# audio_board.net
KiCad netlist of a schematic drawn in EAGLE
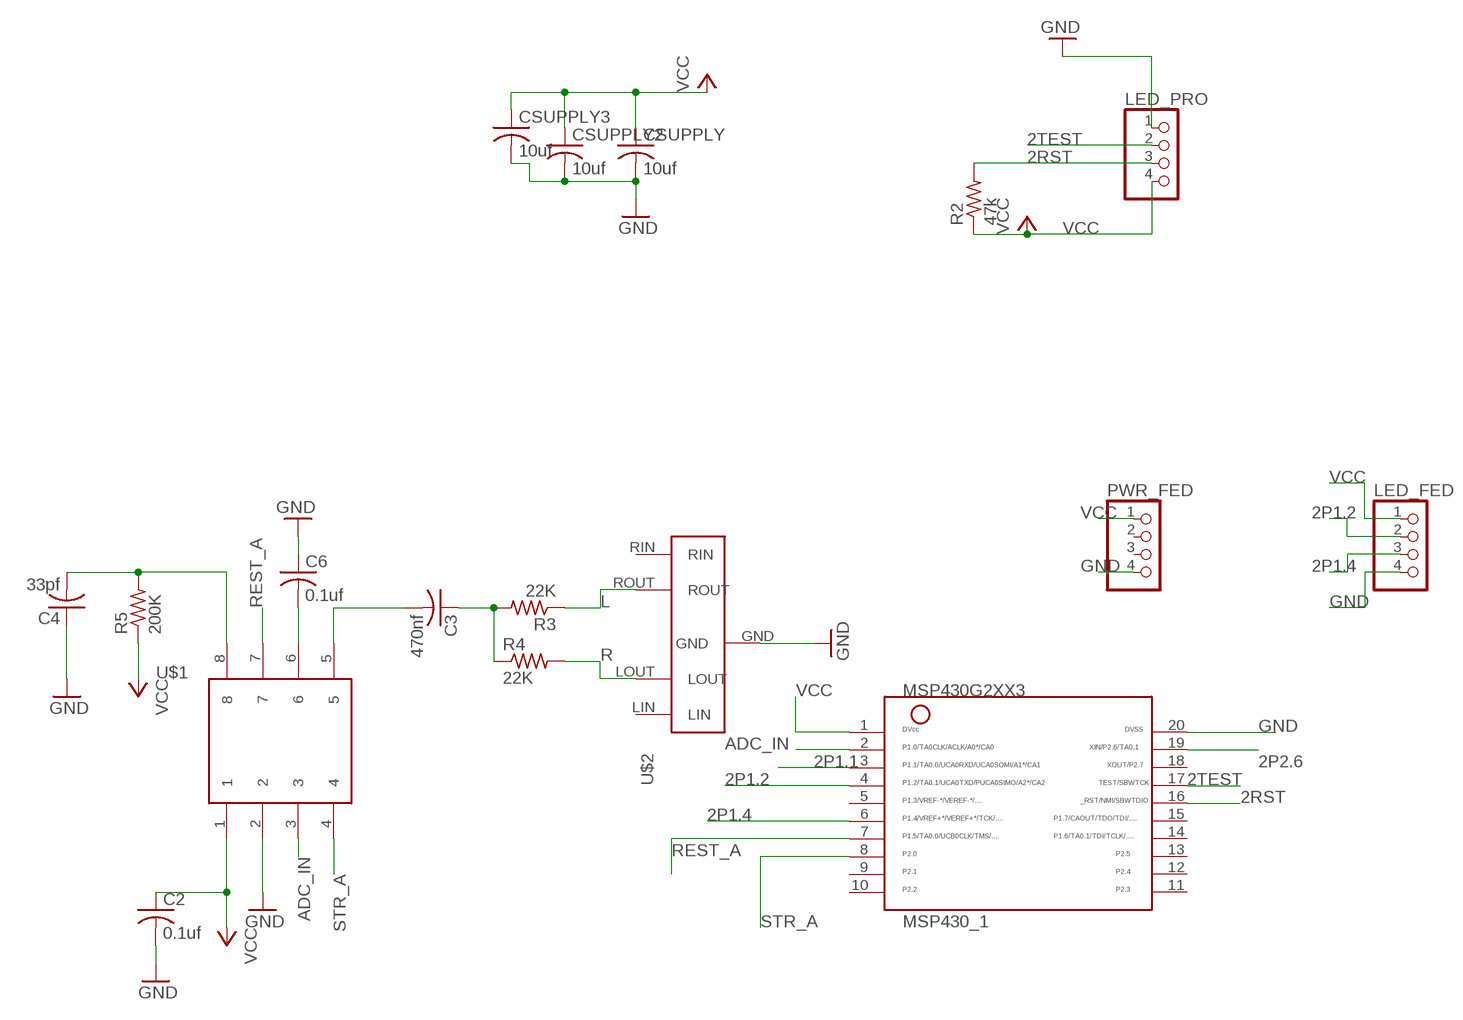
[diagram p0: schematic, sheet 1]

(export (version "E")
  (design (tool "Eeschema 10.0.6"))
  (components
    (comp (ref "C2")
      (value "0.1uf")
      (footprint "eagle-import:C1206")
      (libsource (lib "eagle-import") (part "C-USC1206"))
    )
    (comp (ref "C3")
      (value "470nf")
      (footprint "eagle-import:C1206")
      (libsource (lib "eagle-import") (part "C-USC1206"))
    )
    (comp (ref "C4")
      (value "33pf")
      (footprint "eagle-import:C1206")
      (libsource (lib "eagle-import") (part "C-USC1206"))
    )
    (comp (ref "C6")
      (value "0.1uf")
      (footprint "eagle-import:C1206")
      (libsource (lib "eagle-import") (part "C-USC1206"))
    )
    (comp (ref "CSUPPLY")
      (value "10uf")
      (footprint "eagle-import:C1206")
      (libsource (lib "eagle-import") (part "C-USC1206"))
    )
    (comp (ref "CSUPPLY2")
      (value "10uf")
      (footprint "eagle-import:C1206")
      (libsource (lib "eagle-import") (part "C-USC1206"))
    )
    (comp (ref "CSUPPLY3")
      (value "10uf")
      (footprint "eagle-import:C1206")
      (libsource (lib "eagle-import") (part "C-USC1206"))
    )
    (comp (ref "LED_FED")
      (value "PINHD-1X4")
      (footprint "eagle-import:1X04")
      (libsource (lib "eagle-import") (part "PINHD-1X4"))
    )
    (comp (ref "LED_PRO")
      (value "PINHD-1X4")
      (footprint "eagle-import:1X04")
      (libsource (lib "eagle-import") (part "PINHD-1X4"))
    )
    (comp (ref "MSP430_1")
      (value "MSP430G2XX3TSSOP")
      (footprint "eagle-import:PW20")
      (libsource (lib "eagle-import") (part "MSP430G2XX3TSSOP"))
    )
    (comp (ref "PWR_FED")
      (value "PINHD-1X4")
      (footprint "eagle-import:1X04")
      (libsource (lib "eagle-import") (part "PINHD-1X4"))
    )
    (comp (ref "R2")
      (value "47k")
      (footprint "eagle-import:R1206")
      (libsource (lib "eagle-import") (part "R-US_R1206"))
    )
    (comp (ref "R3")
      (value "22K")
      (footprint "eagle-import:R1206")
      (libsource (lib "eagle-import") (part "R-US_R1206"))
    )
    (comp (ref "R4")
      (value "22K")
      (footprint "eagle-import:R1206")
      (libsource (lib "eagle-import") (part "R-US_R1206"))
    )
    (comp (ref "R5")
      (value "200K")
      (footprint "eagle-import:R1206")
      (libsource (lib "eagle-import") (part "R-US_R1206"))
    )
    (comp (ref "U$1")
      (value "MSGEQ7")
      (footprint "eagle-import:MSGEQ7")
      (libsource (lib "eagle-import") (part "MSGEQ7"))
    )
    (comp (ref "U$2")
      (value "1699_HEAD")
      (footprint "eagle-import:1699_HEAD")
      (libsource (lib "eagle-import") (part "1699_HEAD"))
    )
  )
  (nets
    (net (code "1") (name "/2P1.1") (class "Default")
      (node (ref "MSP430_1") (pin "3") (pinfunction "3_3") (pintype "bidirectional"))
    )
    (net (code "2") (name "/2P1.2") (class "Default")
      (node (ref "LED_FED") (pin "2") (pinfunction "2_2") (pintype "passive"))
      (node (ref "MSP430_1") (pin "4") (pinfunction "4_4") (pintype "bidirectional"))
    )
    (net (code "3") (name "/2P1.4") (class "Default")
      (node (ref "LED_FED") (pin "3") (pinfunction "3_3") (pintype "passive"))
      (node (ref "MSP430_1") (pin "6") (pinfunction "6_6") (pintype "bidirectional"))
    )
    (net (code "4") (name "/2P2.6") (class "Default")
      (node (ref "MSP430_1") (pin "19") (pinfunction "19_19") (pintype "bidirectional"))
    )
    (net (code "5") (name "/2RST") (class "Default")
      (node (ref "LED_PRO") (pin "3") (pinfunction "3_3") (pintype "passive"))
      (node (ref "MSP430_1") (pin "16") (pinfunction "16_16") (pintype "bidirectional"))
      (node (ref "R2") (pin "2") (pinfunction "2_2") (pintype "passive"))
    )
    (net (code "6") (name "/2TEST") (class "Default")
      (node (ref "LED_PRO") (pin "2") (pinfunction "2_2") (pintype "passive"))
      (node (ref "MSP430_1") (pin "17") (pinfunction "17_17") (pintype "bidirectional"))
    )
    (net (code "7") (name "/ADC_IN") (class "Default")
      (node (ref "MSP430_1") (pin "2") (pinfunction "2_2") (pintype "bidirectional"))
      (node (ref "U$1") (pin "3") (pinfunction "3_3") (pintype "bidirectional"))
    )
    (net (code "8") (name "/L") (class "Default")
      (node (ref "R3") (pin "1") (pinfunction "1_1") (pintype "passive"))
      (node (ref "U$2") (pin "ROUT") (pinfunction "ROUT_ROUT") (pintype "bidirectional"))
    )
    (net (code "9") (name "/R") (class "Default")
      (node (ref "R4") (pin "2") (pinfunction "2_2") (pintype "passive"))
      (node (ref "U$2") (pin "LOUT") (pinfunction "LOUT_LOUT") (pintype "bidirectional"))
    )
    (net (code "10") (name "/REST_A") (class "Default")
      (node (ref "MSP430_1") (pin "7") (pinfunction "7_7") (pintype "bidirectional"))
      (node (ref "U$1") (pin "7") (pinfunction "7_7") (pintype "bidirectional"))
    )
    (net (code "11") (name "/STR_A") (class "Default")
      (node (ref "MSP430_1") (pin "8") (pinfunction "8_8") (pintype "bidirectional"))
      (node (ref "U$1") (pin "4") (pinfunction "4_4") (pintype "bidirectional"))
    )
    (net (code "12") (name "GND") (class "Default")
      (node (ref "C2") (pin "2") (pinfunction "2_2") (pintype "passive"))
      (node (ref "C4") (pin "1") (pinfunction "1_1") (pintype "passive"))
      (node (ref "C6") (pin "1") (pinfunction "1_1") (pintype "passive"))
      (node (ref "CSUPPLY") (pin "2") (pinfunction "2_2") (pintype "passive"))
      (node (ref "CSUPPLY2") (pin "2") (pinfunction "2_2") (pintype "passive"))
      (node (ref "CSUPPLY3") (pin "2") (pinfunction "2_2") (pintype "passive"))
      (node (ref "LED_FED") (pin "4") (pinfunction "4_4") (pintype "passive"))
      (node (ref "LED_PRO") (pin "1") (pinfunction "1_1") (pintype "passive"))
      (node (ref "MSP430_1") (pin "20") (pinfunction "20_20") (pintype "bidirectional"))
      (node (ref "PWR_FED") (pin "4") (pinfunction "4_4") (pintype "passive"))
      (node (ref "U$1") (pin "2") (pinfunction "2_2") (pintype "bidirectional"))
      (node (ref "U$2") (pin "GND") (pinfunction "GND_GND") (pintype "bidirectional"))
    )
    (net (code "13") (name "Net-(C3-Pad1)") (class "Default")
      (node (ref "C3") (pin "1") (pinfunction "1_1") (pintype "passive"))
      (node (ref "R3") (pin "2") (pinfunction "2_2") (pintype "passive"))
      (node (ref "R4") (pin "1") (pinfunction "1_1") (pintype "passive"))
    )
    (net (code "14") (name "Net-(C3-Pad2)") (class "Default")
      (node (ref "C3") (pin "2") (pinfunction "2_2") (pintype "passive"))
      (node (ref "U$1") (pin "5") (pinfunction "5_5") (pintype "bidirectional"))
    )
    (net (code "15") (name "Net-(C4-Pad2)") (class "Default")
      (node (ref "C4") (pin "2") (pinfunction "2_2") (pintype "passive"))
      (node (ref "R5") (pin "2") (pinfunction "2_2") (pintype "passive"))
      (node (ref "U$1") (pin "8") (pinfunction "8_8") (pintype "bidirectional"))
    )
    (net (code "16") (name "Net-(C6-Pad2)") (class "Default")
      (node (ref "C6") (pin "2") (pinfunction "2_2") (pintype "passive"))
      (node (ref "U$1") (pin "6") (pinfunction "6_6") (pintype "bidirectional"))
    )
    (net (code "17") (name "VCC") (class "Default")
      (node (ref "C2") (pin "1") (pinfunction "1_1") (pintype "passive"))
      (node (ref "CSUPPLY") (pin "1") (pinfunction "1_1") (pintype "passive"))
      (node (ref "CSUPPLY2") (pin "1") (pinfunction "1_1") (pintype "passive"))
      (node (ref "CSUPPLY3") (pin "1") (pinfunction "1_1") (pintype "passive"))
      (node (ref "LED_FED") (pin "1") (pinfunction "1_1") (pintype "passive"))
      (node (ref "LED_PRO") (pin "4") (pinfunction "4_4") (pintype "passive"))
      (node (ref "MSP430_1") (pin "1") (pinfunction "1_1") (pintype "bidirectional"))
      (node (ref "PWR_FED") (pin "1") (pinfunction "1_1") (pintype "passive"))
      (node (ref "R2") (pin "1") (pinfunction "1_1") (pintype "passive"))
      (node (ref "R5") (pin "1") (pinfunction "1_1") (pintype "passive"))
      (node (ref "U$1") (pin "1") (pinfunction "1_1") (pintype "bidirectional"))
    )
    (net (code "18") (name "unconnected-(MSP430_1-Pad5)") (class "Default")
      (node (ref "MSP430_1") (pin "5") (pinfunction "5_5") (pintype "bidirectional"))
    )
    (net (code "19") (name "unconnected-(MSP430_1-Pad9)") (class "Default")
      (node (ref "MSP430_1") (pin "9") (pinfunction "9_9") (pintype "bidirectional"))
    )
    (net (code "20") (name "unconnected-(MSP430_1-Pad10)") (class "Default")
      (node (ref "MSP430_1") (pin "10") (pinfunction "10_10") (pintype "bidirectional"))
    )
    (net (code "21") (name "unconnected-(MSP430_1-Pad11)") (class "Default")
      (node (ref "MSP430_1") (pin "11") (pinfunction "11_11") (pintype "bidirectional"))
    )
    (net (code "22") (name "unconnected-(MSP430_1-Pad12)") (class "Default")
      (node (ref "MSP430_1") (pin "12") (pinfunction "12_12") (pintype "bidirectional"))
    )
    (net (code "23") (name "unconnected-(MSP430_1-Pad13)") (class "Default")
      (node (ref "MSP430_1") (pin "13") (pinfunction "13_13") (pintype "bidirectional"))
    )
    (net (code "24") (name "unconnected-(MSP430_1-Pad14)") (class "Default")
      (node (ref "MSP430_1") (pin "14") (pinfunction "14_14") (pintype "bidirectional"))
    )
    (net (code "25") (name "unconnected-(MSP430_1-Pad15)") (class "Default")
      (node (ref "MSP430_1") (pin "15") (pinfunction "15_15") (pintype "bidirectional"))
    )
    (net (code "26") (name "unconnected-(MSP430_1-Pad18)") (class "Default")
      (node (ref "MSP430_1") (pin "18") (pinfunction "18_18") (pintype "bidirectional"))
    )
    (net (code "27") (name "unconnected-(PWR_FED-Pad2)") (class "Default")
      (node (ref "PWR_FED") (pin "2") (pinfunction "2_2") (pintype "passive"))
    )
    (net (code "28") (name "unconnected-(PWR_FED-Pad3)") (class "Default")
      (node (ref "PWR_FED") (pin "3") (pinfunction "3_3") (pintype "passive"))
    )
    (net (code "29") (name "unconnected-(U$2-PadLIN)") (class "Default")
      (node (ref "U$2") (pin "LIN") (pinfunction "LIN_LIN") (pintype "bidirectional"))
    )
    (net (code "30") (name "unconnected-(U$2-PadRIN)") (class "Default")
      (node (ref "U$2") (pin "RIN") (pinfunction "RIN_RIN") (pintype "bidirectional"))
    )
  )
)
